# VCA.net
KiCad netlist of a schematic drawn in Altium Designer
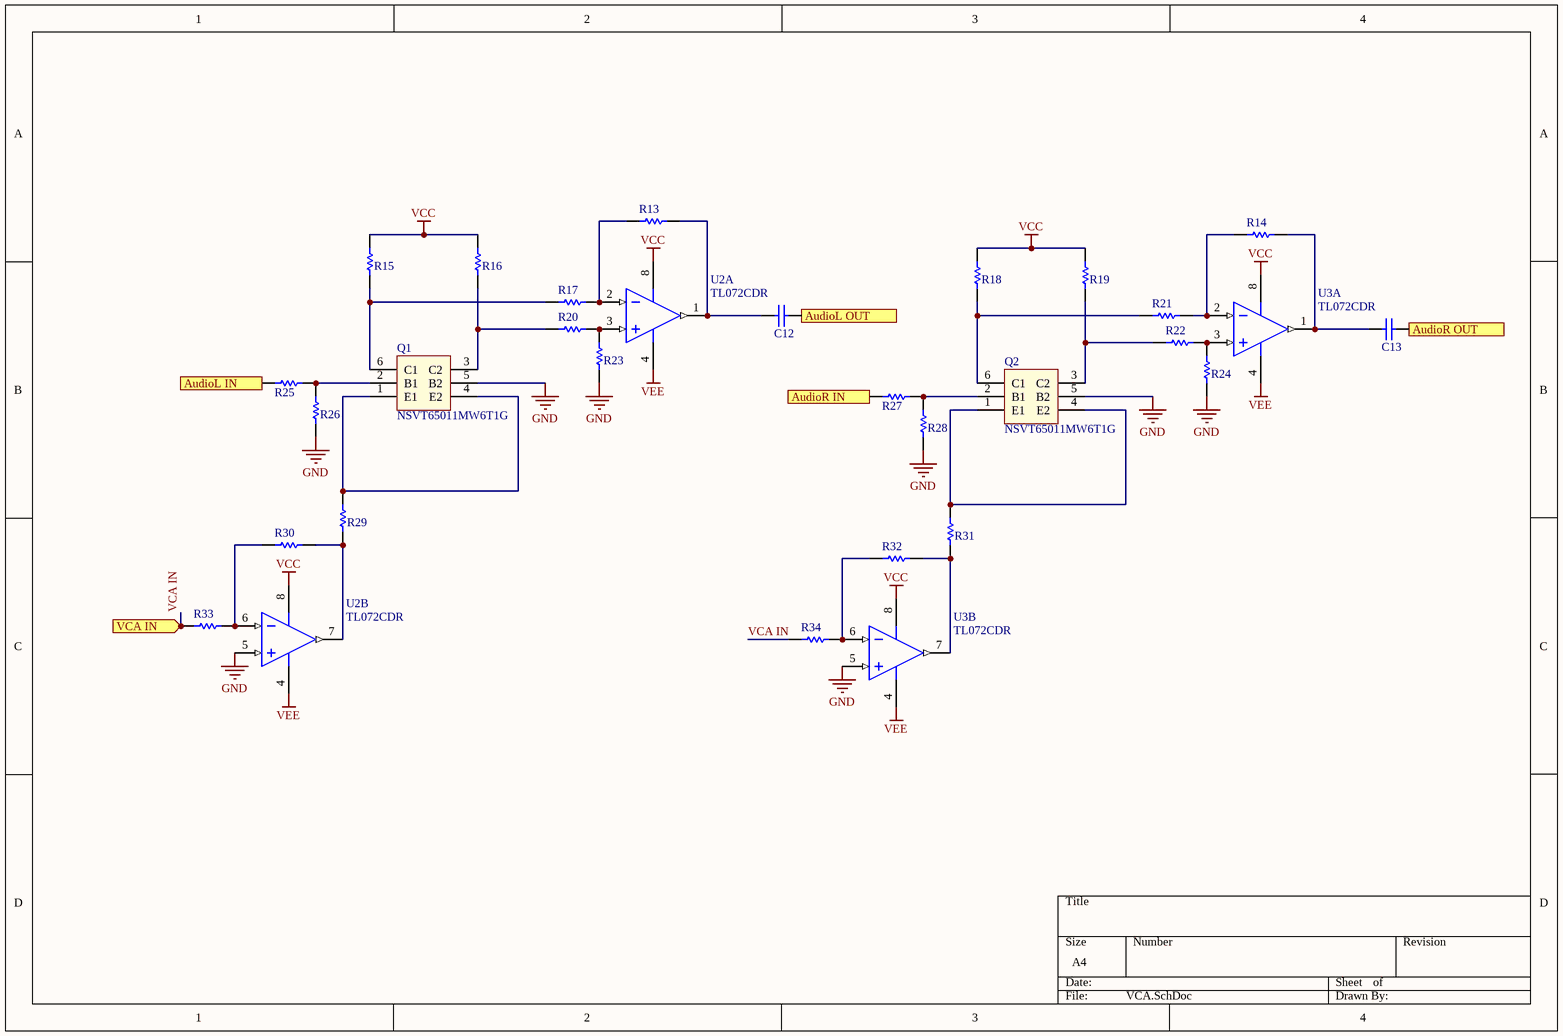
[diagram p0: VCA.SchDoc]

(export (version "E")
  (design (tool "Eeschema 10.0.6"))
  (components
    (comp (ref "C12")
      (value "1206GC102KAT1A")
      (footprint "AVX-1206-2_L")
      (description "Chip Capacitor, 1 nF, +/- 10%, -55 to 125 degC, 1206 (3216 Metric), RoHS, Tape and Reel")
      (fields (field (name "TOLERANCE") "10%") (field (name "MANUFACTURER") "AVX"))
      (libsource (lib "Altium Content Vault") (part "CAP-NP-2"))
    )
    (comp (ref "C13")
      (value "1206GC102KAT1A")
      (footprint "AVX-1206-2_L")
      (description "Chip Capacitor, 1 nF, +/- 10%, -55 to 125 degC, 1206 (3216 Metric), RoHS, Tape and Reel")
      (fields (field (name "TOLERANCE") "10%") (field (name "MANUFACTURER") "AVX"))
      (libsource (lib "Altium Content Vault") (part "CAP-NP-2"))
    )
    (comp (ref "Q1")
      (value "NSVT65011MW6T1G")
      (footprint "NSVT65011MW6T1G")
      (libsource (lib "Schlib") (part "NSVT65011MW6T1G"))
    )
    (comp (ref "Q2")
      (value "NSVT65011MW6T1G")
      (footprint "NSVT65011MW6T1G")
      (libsource (lib "Schlib") (part "NSVT65011MW6T1G"))
    )
    (comp (ref "R13")
      (value "ERJ-8GEY0R00V")
      (footprint "RESC3216X70X50NL05T20")
      (fields (field (name "MANUFACTURER") "Panasonic"))
      (libsource (lib "Altium Content Vault") (part "RES"))
    )
    (comp (ref "R14")
      (value "ERJ-8GEY0R00V")
      (footprint "RESC3216X70X50NL05T20")
      (fields (field (name "MANUFACTURER") "Panasonic"))
      (libsource (lib "Altium Content Vault") (part "RES"))
    )
    (comp (ref "R15")
      (value "ERJ-8GEY0R00V")
      (footprint "RESC3216X70X50NL05T20")
      (fields (field (name "MANUFACTURER") "Panasonic"))
      (libsource (lib "Altium Content Vault") (part "RES"))
    )
    (comp (ref "R16")
      (value "ERJ-8GEY0R00V")
      (footprint "RESC3216X70X50NL05T20")
      (fields (field (name "MANUFACTURER") "Panasonic"))
      (libsource (lib "Altium Content Vault") (part "RES"))
    )
    (comp (ref "R17")
      (value "ERJ-8GEY0R00V")
      (footprint "RESC3216X70X50NL05T20")
      (fields (field (name "MANUFACTURER") "Panasonic"))
      (libsource (lib "Altium Content Vault") (part "RES"))
    )
    (comp (ref "R18")
      (value "ERJ-8GEY0R00V")
      (footprint "RESC3216X70X50NL05T20")
      (fields (field (name "MANUFACTURER") "Panasonic"))
      (libsource (lib "Altium Content Vault") (part "RES"))
    )
    (comp (ref "R19")
      (value "ERJ-8GEY0R00V")
      (footprint "RESC3216X70X50NL05T20")
      (fields (field (name "MANUFACTURER") "Panasonic"))
      (libsource (lib "Altium Content Vault") (part "RES"))
    )
    (comp (ref "R20")
      (value "ERJ-8GEY0R00V")
      (footprint "RESC3216X70X50NL05T20")
      (fields (field (name "MANUFACTURER") "Panasonic"))
      (libsource (lib "Altium Content Vault") (part "RES"))
    )
    (comp (ref "R21")
      (value "ERJ-8GEY0R00V")
      (footprint "RESC3216X70X50NL05T20")
      (fields (field (name "MANUFACTURER") "Panasonic"))
      (libsource (lib "Altium Content Vault") (part "RES"))
    )
    (comp (ref "R22")
      (value "ERJ-8GEY0R00V")
      (footprint "RESC3216X70X50NL05T20")
      (fields (field (name "MANUFACTURER") "Panasonic"))
      (libsource (lib "Altium Content Vault") (part "RES"))
    )
    (comp (ref "R23")
      (value "ERJ-8GEY0R00V")
      (footprint "RESC3216X70X50NL05T20")
      (fields (field (name "MANUFACTURER") "Panasonic"))
      (libsource (lib "Altium Content Vault") (part "RES"))
    )
    (comp (ref "R24")
      (value "ERJ-8GEY0R00V")
      (footprint "RESC3216X70X50NL05T20")
      (fields (field (name "MANUFACTURER") "Panasonic"))
      (libsource (lib "Altium Content Vault") (part "RES"))
    )
    (comp (ref "R25")
      (value "ERJ-8GEY0R00V")
      (footprint "RESC3216X70X50NL05T20")
      (fields (field (name "MANUFACTURER") "Panasonic"))
      (libsource (lib "Altium Content Vault") (part "RES"))
    )
    (comp (ref "R26")
      (value "ERJ-8GEY0R00V")
      (footprint "RESC3216X70X50NL05T20")
      (fields (field (name "MANUFACTURER") "Panasonic"))
      (libsource (lib "Altium Content Vault") (part "RES"))
    )
    (comp (ref "R27")
      (value "ERJ-8GEY0R00V")
      (footprint "RESC3216X70X50NL05T20")
      (fields (field (name "MANUFACTURER") "Panasonic"))
      (libsource (lib "Altium Content Vault") (part "RES"))
    )
    (comp (ref "R28")
      (value "ERJ-8GEY0R00V")
      (footprint "RESC3216X70X50NL05T20")
      (fields (field (name "MANUFACTURER") "Panasonic"))
      (libsource (lib "Altium Content Vault") (part "RES"))
    )
    (comp (ref "R29")
      (value "ERJ-8GEY0R00V")
      (footprint "RESC3216X70X50NL05T20")
      (fields (field (name "MANUFACTURER") "Panasonic"))
      (libsource (lib "Altium Content Vault") (part "RES"))
    )
    (comp (ref "R30")
      (value "ERJ-8GEY0R00V")
      (footprint "RESC3216X70X50NL05T20")
      (fields (field (name "MANUFACTURER") "Panasonic"))
      (libsource (lib "Altium Content Vault") (part "RES"))
    )
    (comp (ref "R31")
      (value "ERJ-8GEY0R00V")
      (footprint "RESC3216X70X50NL05T20")
      (fields (field (name "MANUFACTURER") "Panasonic"))
      (libsource (lib "Altium Content Vault") (part "RES"))
    )
    (comp (ref "R32")
      (value "ERJ-8GEY0R00V")
      (footprint "RESC3216X70X50NL05T20")
      (fields (field (name "MANUFACTURER") "Panasonic"))
      (libsource (lib "Altium Content Vault") (part "RES"))
    )
    (comp (ref "R33")
      (value "ERJ-8GEY0R00V")
      (footprint "RESC3216X70X50NL05T20")
      (fields (field (name "MANUFACTURER") "Panasonic"))
      (libsource (lib "Altium Content Vault") (part "RES"))
    )
    (comp (ref "R34")
      (value "ERJ-8GEY0R00V")
      (footprint "RESC3216X70X50NL05T20")
      (fields (field (name "MANUFACTURER") "Panasonic"))
      (libsource (lib "Altium Content Vault") (part "RES"))
    )
    (comp (ref "U2")
      (value "TL072CDR")
      (footprint "D0008A_M")
      (fields (field (name "MANUFACTURER") "Texas Instruments"))
      (libsource (lib "Altium Content Vault") (part "TI-AMP-D6-2-8_D"))
    )
    (comp (ref "U3")
      (value "TL072CDR")
      (footprint "D0008A_M")
      (fields (field (name "MANUFACTURER") "Texas Instruments"))
      (libsource (lib "Altium Content Vault") (part "TI-AMP-D6-2-8_D"))
    )
  )
  (nets
    (net (code "1") (name "/AudioL IN") (class "Default")
      (node (ref "R25") (pin "2") (pinfunction "2_2") (pintype "passive"))
    )
    (net (code "2") (name "/AudioL OUT") (class "Default")
      (node (ref "C12") (pin "2") (pinfunction "2_2") (pintype "passive"))
    )
    (net (code "3") (name "/AudioR IN") (class "Default")
      (node (ref "R27") (pin "2") (pinfunction "2_2") (pintype "passive"))
    )
    (net (code "4") (name "/AudioR OUT") (class "Default")
      (node (ref "C13") (pin "2") (pinfunction "2_2") (pintype "passive"))
    )
    (net (code "5") (name "/VCA IN") (class "Default")
      (node (ref "R33") (pin "1") (pinfunction "1_1") (pintype "passive"))
      (node (ref "R34") (pin "1") (pinfunction "1_1") (pintype "passive"))
    )
    (net (code "6") (name "GND") (class "Default")
      (node (ref "Q1") (pin "5") (pinfunction "B2_5") (pintype "passive"))
      (node (ref "Q2") (pin "5") (pinfunction "B2_5") (pintype "passive"))
      (node (ref "R23") (pin "1") (pinfunction "1_1") (pintype "passive"))
      (node (ref "R24") (pin "1") (pinfunction "1_1") (pintype "passive"))
      (node (ref "R26") (pin "1") (pinfunction "1_1") (pintype "passive"))
      (node (ref "R28") (pin "1") (pinfunction "1_1") (pintype "passive"))
      (node (ref "U2") (pin "5") (pinfunction "IN2+_5") (pintype "input"))
      (node (ref "U3") (pin "5") (pinfunction "IN2+_5") (pintype "input"))
    )
    (net (code "7") (name "Net-(Q1-B1)") (class "Default")
      (node (ref "Q1") (pin "2") (pinfunction "B1_2") (pintype "passive"))
      (node (ref "R25") (pin "1") (pinfunction "1_1") (pintype "passive"))
      (node (ref "R26") (pin "2") (pinfunction "2_2") (pintype "passive"))
    )
    (net (code "8") (name "Net-(Q1-C1)") (class "Default")
      (node (ref "Q1") (pin "6") (pinfunction "C1_6") (pintype "passive"))
      (node (ref "R15") (pin "1") (pinfunction "1_1") (pintype "passive"))
      (node (ref "R17") (pin "1") (pinfunction "1_1") (pintype "passive"))
    )
    (net (code "9") (name "Net-(Q1-C2)") (class "Default")
      (node (ref "Q1") (pin "3") (pinfunction "C2_3") (pintype "passive"))
      (node (ref "R16") (pin "1") (pinfunction "1_1") (pintype "passive"))
      (node (ref "R20") (pin "1") (pinfunction "1_1") (pintype "passive"))
    )
    (net (code "10") (name "Net-(Q1-E1)") (class "Default")
      (node (ref "Q1") (pin "1") (pinfunction "E1_1") (pintype "passive"))
      (node (ref "Q1") (pin "4") (pinfunction "E2_4") (pintype "passive"))
      (node (ref "R29") (pin "2") (pinfunction "2_2") (pintype "passive"))
    )
    (net (code "11") (name "Net-(Q2-B1)") (class "Default")
      (node (ref "Q2") (pin "2") (pinfunction "B1_2") (pintype "passive"))
      (node (ref "R27") (pin "1") (pinfunction "1_1") (pintype "passive"))
      (node (ref "R28") (pin "2") (pinfunction "2_2") (pintype "passive"))
    )
    (net (code "12") (name "Net-(Q2-C1)") (class "Default")
      (node (ref "Q2") (pin "6") (pinfunction "C1_6") (pintype "passive"))
      (node (ref "R18") (pin "1") (pinfunction "1_1") (pintype "passive"))
      (node (ref "R21") (pin "1") (pinfunction "1_1") (pintype "passive"))
    )
    (net (code "13") (name "Net-(Q2-C2)") (class "Default")
      (node (ref "Q2") (pin "3") (pinfunction "C2_3") (pintype "passive"))
      (node (ref "R19") (pin "1") (pinfunction "1_1") (pintype "passive"))
      (node (ref "R22") (pin "1") (pinfunction "1_1") (pintype "passive"))
    )
    (net (code "14") (name "Net-(Q2-E1)") (class "Default")
      (node (ref "Q2") (pin "1") (pinfunction "E1_1") (pintype "passive"))
      (node (ref "Q2") (pin "4") (pinfunction "E2_4") (pintype "passive"))
      (node (ref "R31") (pin "2") (pinfunction "2_2") (pintype "passive"))
    )
    (net (code "15") (name "Net-(U2A-IN1+)") (class "Default")
      (node (ref "R20") (pin "2") (pinfunction "2_2") (pintype "passive"))
      (node (ref "R23") (pin "2") (pinfunction "2_2") (pintype "passive"))
      (node (ref "U2") (pin "3") (pinfunction "IN1+_3") (pintype "input"))
    )
    (net (code "16") (name "Net-(U2A-IN1-)") (class "Default")
      (node (ref "R13") (pin "1") (pinfunction "1_1") (pintype "passive"))
      (node (ref "R17") (pin "2") (pinfunction "2_2") (pintype "passive"))
      (node (ref "U2") (pin "2") (pinfunction "IN1-_2") (pintype "input"))
    )
    (net (code "17") (name "Net-(U2A-OUT1)") (class "Default")
      (node (ref "C12") (pin "1") (pinfunction "1_1") (pintype "passive"))
      (node (ref "R13") (pin "2") (pinfunction "2_2") (pintype "passive"))
      (node (ref "U2") (pin "1") (pinfunction "OUT1_1") (pintype "output"))
    )
    (net (code "18") (name "Net-(U2B-IN2-)") (class "Default")
      (node (ref "R30") (pin "1") (pinfunction "1_1") (pintype "passive"))
      (node (ref "R33") (pin "2") (pinfunction "2_2") (pintype "passive"))
      (node (ref "U2") (pin "6") (pinfunction "IN2-_6") (pintype "input"))
    )
    (net (code "19") (name "Net-(U2B-OUT2)") (class "Default")
      (node (ref "R29") (pin "1") (pinfunction "1_1") (pintype "passive"))
      (node (ref "R30") (pin "2") (pinfunction "2_2") (pintype "passive"))
      (node (ref "U2") (pin "7") (pinfunction "OUT2_7") (pintype "output"))
    )
    (net (code "20") (name "Net-(U3A-IN1+)") (class "Default")
      (node (ref "R22") (pin "2") (pinfunction "2_2") (pintype "passive"))
      (node (ref "R24") (pin "2") (pinfunction "2_2") (pintype "passive"))
      (node (ref "U3") (pin "3") (pinfunction "IN1+_3") (pintype "input"))
    )
    (net (code "21") (name "Net-(U3A-IN1-)") (class "Default")
      (node (ref "R14") (pin "1") (pinfunction "1_1") (pintype "passive"))
      (node (ref "R21") (pin "2") (pinfunction "2_2") (pintype "passive"))
      (node (ref "U3") (pin "2") (pinfunction "IN1-_2") (pintype "input"))
    )
    (net (code "22") (name "Net-(U3A-OUT1)") (class "Default")
      (node (ref "C13") (pin "1") (pinfunction "1_1") (pintype "passive"))
      (node (ref "R14") (pin "2") (pinfunction "2_2") (pintype "passive"))
      (node (ref "U3") (pin "1") (pinfunction "OUT1_1") (pintype "output"))
    )
    (net (code "23") (name "Net-(U3B-IN2-)") (class "Default")
      (node (ref "R32") (pin "1") (pinfunction "1_1") (pintype "passive"))
      (node (ref "R34") (pin "2") (pinfunction "2_2") (pintype "passive"))
      (node (ref "U3") (pin "6") (pinfunction "IN2-_6") (pintype "input"))
    )
    (net (code "24") (name "Net-(U3B-OUT2)") (class "Default")
      (node (ref "R31") (pin "1") (pinfunction "1_1") (pintype "passive"))
      (node (ref "R32") (pin "2") (pinfunction "2_2") (pintype "passive"))
      (node (ref "U3") (pin "7") (pinfunction "OUT2_7") (pintype "output"))
    )
    (net (code "25") (name "VCC") (class "Default")
      (node (ref "R15") (pin "2") (pinfunction "2_2") (pintype "passive"))
      (node (ref "R16") (pin "2") (pinfunction "2_2") (pintype "passive"))
      (node (ref "R18") (pin "2") (pinfunction "2_2") (pintype "passive"))
      (node (ref "R19") (pin "2") (pinfunction "2_2") (pintype "passive"))
      (node (ref "U2") (pin "8") (pinfunction "VCC+_8") (pintype "power_in"))
      (node (ref "U3") (pin "8") (pinfunction "VCC+_8") (pintype "power_in"))
    )
    (net (code "26") (name "VEE") (class "Default")
      (node (ref "U2") (pin "4") (pinfunction "VCC-_4") (pintype "power_in"))
      (node (ref "U3") (pin "4") (pinfunction "VCC-_4") (pintype "power_in"))
    )
  )
)
